# source_eagle.net
KiCad netlist of a schematic drawn in EAGLE
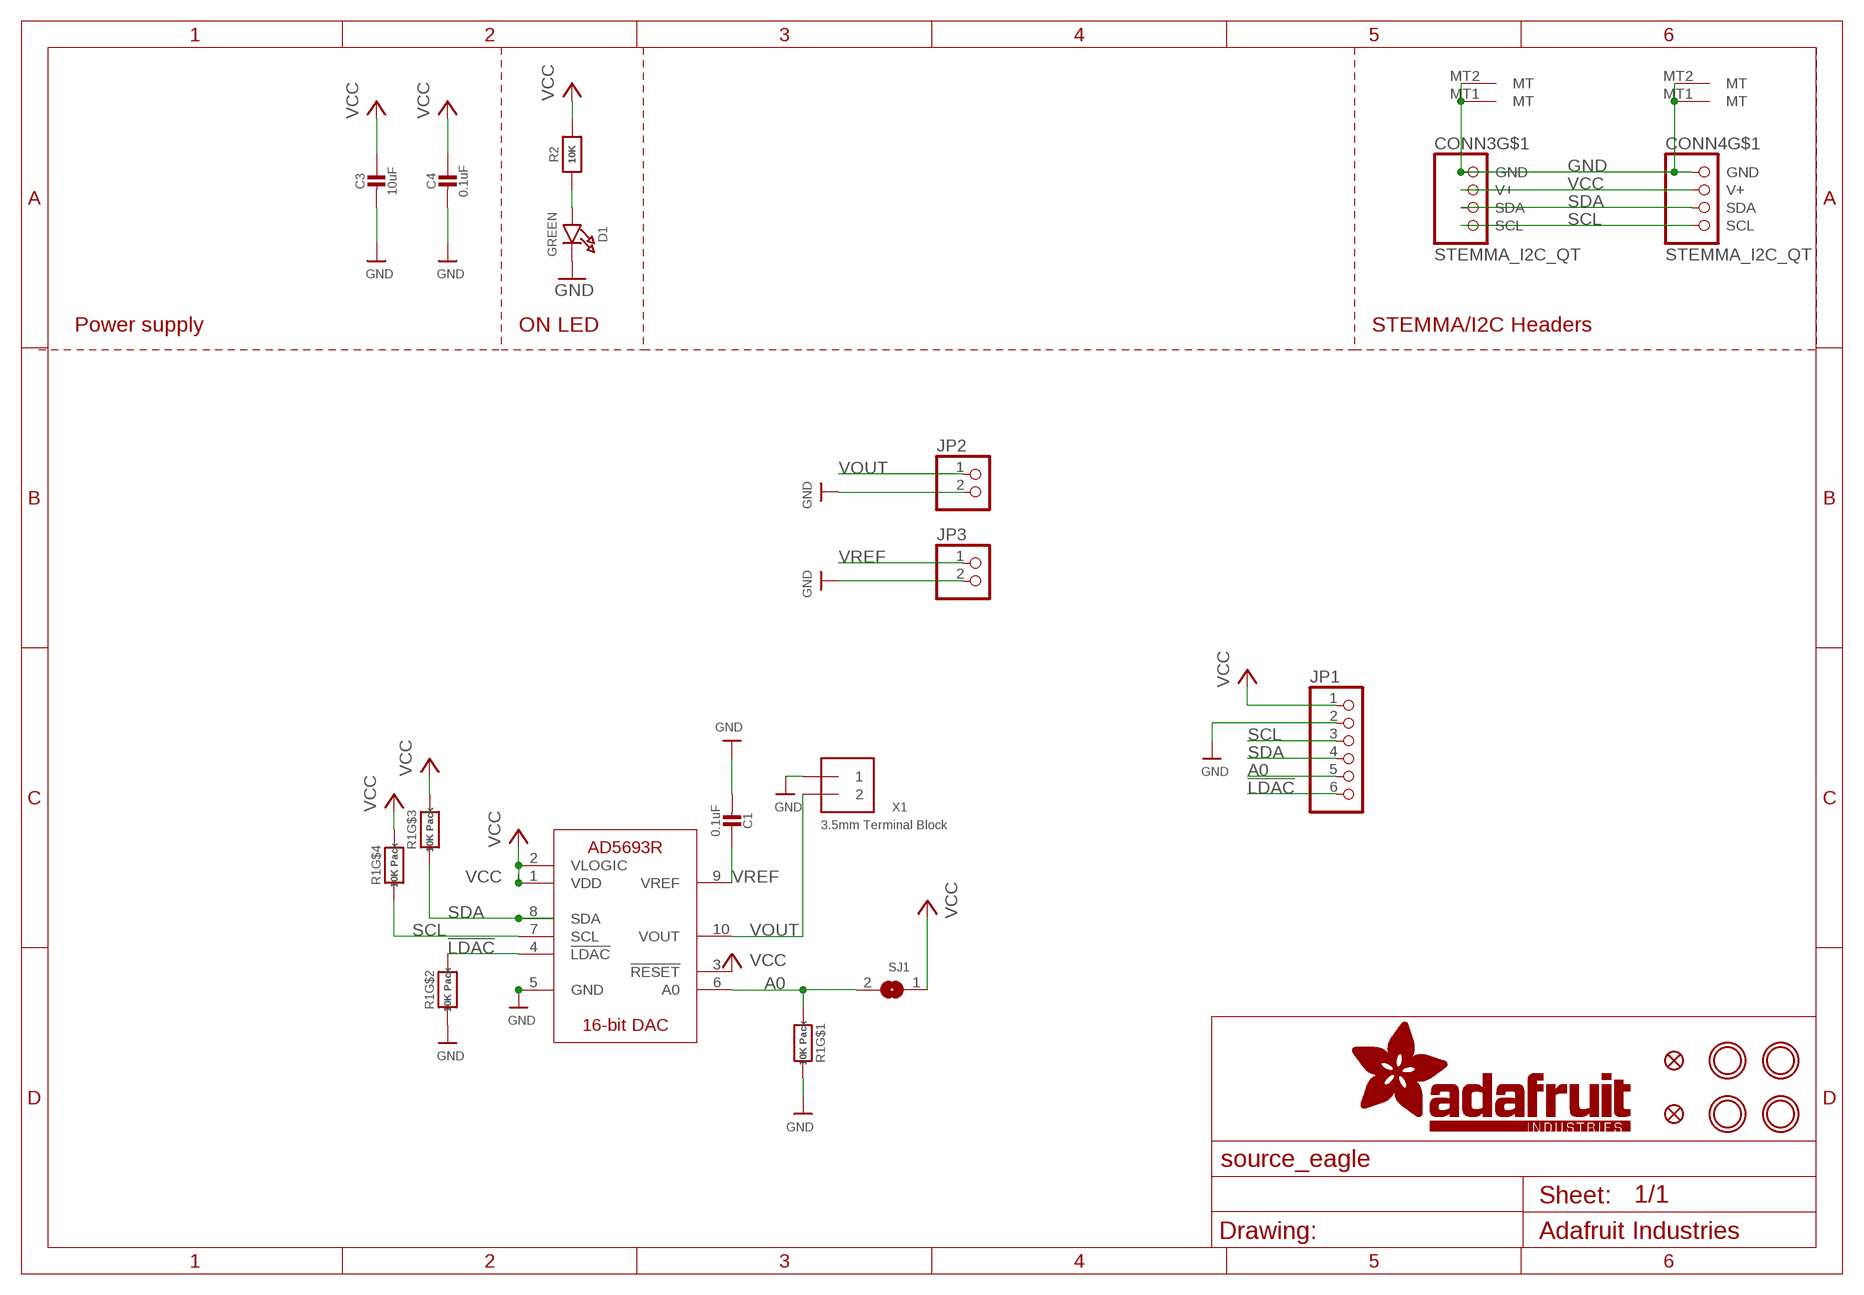
[diagram p0: schematic, sheet 1]

(export (version "E")
  (design (tool "Eeschema 10.0.6"))
  (components
    (comp (ref "C1")
      (value "0.1uF")
      (footprint "eagle-import:0603-NO")
      (libsource (lib "eagle-import") (part "CAP_CERAMIC0603_NO"))
    )
    (comp (ref "C3")
      (value "10uF")
      (footprint "eagle-import:0805-NO")
      (libsource (lib "eagle-import") (part "CAP_CERAMIC0805-NOOUTLINE"))
    )
    (comp (ref "C4")
      (value "0.1uF")
      (footprint "eagle-import:0603-NO")
      (libsource (lib "eagle-import") (part "CAP_CERAMIC0603_NO"))
    )
    (comp (ref "CONN3")
      (value "STEMMA_I2C_QT")
      (footprint "eagle-import:JST_SH4")
      (libsource (lib "eagle-import") (part "STEMMA_I2C_QT"))
    )
    (comp (ref "CONN4")
      (value "STEMMA_I2C_QT")
      (footprint "eagle-import:JST_SH4")
      (libsource (lib "eagle-import") (part "STEMMA_I2C_QT"))
    )
    (comp (ref "D1")
      (value "GREEN")
      (footprint "eagle-import:CHIPLED_0603_NOOUTLINE")
      (libsource (lib "eagle-import") (part "LED0603_NOOUTLINE"))
    )
    (comp (ref "FID3")
      (value "FIDUCIAL_1MM")
      (footprint "eagle-import:FIDUCIAL_1MM")
      (libsource (lib "eagle-import") (part "FIDUCIAL_1MM"))
    )
    (comp (ref "FID4")
      (value "FIDUCIAL_1MM")
      (footprint "eagle-import:FIDUCIAL_1MM")
      (libsource (lib "eagle-import") (part "FIDUCIAL_1MM"))
    )
    (comp (ref "IC2")
      (value "AD5693R_10PIN_RMZ")
      (footprint "eagle-import:MSOP10")
      (libsource (lib "eagle-import") (part "AD5693R_10PIN_RMZ"))
    )
    (comp (ref "JP1")
      (value "HEADER-1X670MIL")
      (footprint "eagle-import:1X06_ROUND_70")
      (libsource (lib "eagle-import") (part "HEADER-1X670MIL"))
    )
    (comp (ref "JP2")
      (value "HEADER-1X2ROUND")
      (footprint "eagle-import:1X02_ROUND")
      (libsource (lib "eagle-import") (part "HEADER-1X2ROUND"))
    )
    (comp (ref "JP3")
      (value "HEADER-1X2ROUND")
      (footprint "eagle-import:1X02_ROUND")
      (libsource (lib "eagle-import") (part "HEADER-1X2ROUND"))
    )
    (comp (ref "R1")
      (value "10K Pack")
      (footprint "eagle-import:RESPACK_4X0603")
      (libsource (lib "eagle-import") (part "RESISTOR_4PACK"))
    )
    (comp (ref "R2")
      (value "10K")
      (footprint "eagle-import:0603-NO")
      (libsource (lib "eagle-import") (part "RESISTOR_0603_NOOUT"))
    )
    (comp (ref "SJ1")
      (value "SOLDERJUMPER")
      (footprint "eagle-import:SOLDERJUMPER_ARROW_NOPASTE")
      (libsource (lib "eagle-import") (part "SOLDERJUMPER"))
    )
    (comp (ref "U$20")
      (value "MOUNTINGHOLE2.5")
      (footprint "eagle-import:MOUNTINGHOLE_2.5_PLATED")
      (libsource (lib "eagle-import") (part "MOUNTINGHOLE2.5"))
    )
    (comp (ref "U$21")
      (value "MOUNTINGHOLE2.5")
      (footprint "eagle-import:MOUNTINGHOLE_2.5_PLATED")
      (libsource (lib "eagle-import") (part "MOUNTINGHOLE2.5"))
    )
    (comp (ref "U$25")
      (value "MOUNTINGHOLE2.5")
      (footprint "eagle-import:MOUNTINGHOLE_2.5_PLATED")
      (libsource (lib "eagle-import") (part "MOUNTINGHOLE2.5"))
    )
    (comp (ref "U$27")
      (value "MOUNTINGHOLE2.5")
      (footprint "eagle-import:MOUNTINGHOLE_2.5_PLATED")
      (libsource (lib "eagle-import") (part "MOUNTINGHOLE2.5"))
    )
    (comp (ref "X1")
      (value "3.5mm Terminal Block")
      (footprint "eagle-import:TERMBLOCK_1X2-3.5MM")
      (libsource (lib "eagle-import") (part "TERMBLOCK_1X2_3.5MM"))
    )
  )
  (nets
    (net (code "1") (name "/A0") (class "Default")
      (node (ref "IC2") (pin "6") (pinfunction "A0_6") (pintype "input"))
      (node (ref "JP1") (pin "5") (pinfunction "5_5") (pintype "passive"))
      (node (ref "R1") (pin "8") (pinfunction "2_8") (pintype "passive"))
      (node (ref "SJ1") (pin "2") (pinfunction "2_2") (pintype "passive"))
    )
    (net (code "2") (name "/SCL") (class "Default")
      (node (ref "CONN3") (pin "4") (pinfunction "SCL_4") (pintype "passive"))
      (node (ref "CONN4") (pin "4") (pinfunction "SCL_4") (pintype "passive"))
      (node (ref "IC2") (pin "7") (pinfunction "SCL_7") (pintype "bidirectional"))
      (node (ref "JP1") (pin "3") (pinfunction "3_3") (pintype "passive"))
      (node (ref "R1") (pin "4") (pinfunction "1_4") (pintype "passive"))
    )
    (net (code "3") (name "/SDA") (class "Default")
      (node (ref "CONN3") (pin "3") (pinfunction "SDA_3") (pintype "passive"))
      (node (ref "CONN4") (pin "3") (pinfunction "SDA_3") (pintype "passive"))
      (node (ref "IC2") (pin "8") (pinfunction "SDA_8") (pintype "bidirectional"))
      (node (ref "JP1") (pin "4") (pinfunction "4_4") (pintype "passive"))
      (node (ref "R1") (pin "3") (pinfunction "1_3") (pintype "passive"))
    )
    (net (code "4") (name "/VOUT") (class "Default")
      (node (ref "IC2") (pin "10") (pinfunction "VOUT_10") (pintype "output"))
      (node (ref "JP2") (pin "1") (pinfunction "1_1") (pintype "passive"))
      (node (ref "X1") (pin "2") (pinfunction "2_2") (pintype "passive"))
    )
    (net (code "5") (name "/VREF") (class "Default")
      (node (ref "C1") (pin "1") (pinfunction "1_1") (pintype "passive"))
      (node (ref "IC2") (pin "9") (pinfunction "VREF_9") (pintype "power_in"))
      (node (ref "JP3") (pin "1") (pinfunction "1_1") (pintype "passive"))
    )
    (net (code "6") (name "/~{LDAC}") (class "Default")
      (node (ref "IC2") (pin "4") (pinfunction "~{LDAC}_4") (pintype "input"))
      (node (ref "JP1") (pin "6") (pinfunction "6_6") (pintype "passive"))
      (node (ref "R1") (pin "7") (pinfunction "2_7") (pintype "passive"))
    )
    (net (code "7") (name "GND") (class "Default")
      (node (ref "C1") (pin "2") (pinfunction "2_2") (pintype "passive"))
      (node (ref "C3") (pin "2") (pinfunction "2_2") (pintype "passive"))
      (node (ref "C4") (pin "2") (pinfunction "2_2") (pintype "passive"))
      (node (ref "CONN3") (pin "1") (pinfunction "GND_1") (pintype "passive"))
      (node (ref "CONN3") (pin "MT1") (pinfunction "MT_MT1") (pintype "bidirectional"))
      (node (ref "CONN3") (pin "MT2") (pinfunction "MT_MT2") (pintype "bidirectional"))
      (node (ref "CONN4") (pin "1") (pinfunction "GND_1") (pintype "passive"))
      (node (ref "CONN4") (pin "MT1") (pinfunction "MT_MT1") (pintype "bidirectional"))
      (node (ref "CONN4") (pin "MT2") (pinfunction "MT_MT2") (pintype "bidirectional"))
      (node (ref "D1") (pin "C") (pinfunction "C_C") (pintype "passive"))
      (node (ref "IC2") (pin "5") (pinfunction "GND_5") (pintype "power_in"))
      (node (ref "JP1") (pin "2") (pinfunction "2_2") (pintype "passive"))
      (node (ref "JP2") (pin "2") (pinfunction "2_2") (pintype "passive"))
      (node (ref "JP3") (pin "2") (pinfunction "2_2") (pintype "passive"))
      (node (ref "R1") (pin "1") (pinfunction "1_1") (pintype "passive"))
      (node (ref "R1") (pin "2") (pinfunction "1_2") (pintype "passive"))
      (node (ref "X1") (pin "1") (pinfunction "1_1") (pintype "passive"))
    )
    (net (code "8") (name "Net-(D1-PadA)") (class "Default")
      (node (ref "D1") (pin "A") (pinfunction "A_A") (pintype "passive"))
      (node (ref "R2") (pin "1") (pinfunction "1_1") (pintype "passive"))
    )
    (net (code "9") (name "VCC") (class "Default")
      (node (ref "C3") (pin "1") (pinfunction "1_1") (pintype "passive"))
      (node (ref "C4") (pin "1") (pinfunction "1_1") (pintype "passive"))
      (node (ref "CONN3") (pin "2") (pinfunction "V+_2") (pintype "passive"))
      (node (ref "CONN4") (pin "2") (pinfunction "V+_2") (pintype "passive"))
      (node (ref "IC2") (pin "1") (pinfunction "VDD_1") (pintype "power_in"))
      (node (ref "IC2") (pin "2") (pinfunction "VLOGIC_2") (pintype "power_in"))
      (node (ref "IC2") (pin "3") (pinfunction "~{RESET}_3") (pintype "input"))
      (node (ref "JP1") (pin "1") (pinfunction "1_1") (pintype "passive"))
      (node (ref "R1") (pin "5") (pinfunction "2_5") (pintype "passive"))
      (node (ref "R1") (pin "6") (pinfunction "2_6") (pintype "passive"))
      (node (ref "R2") (pin "2") (pinfunction "2_2") (pintype "passive"))
      (node (ref "SJ1") (pin "1") (pinfunction "1_1") (pintype "passive"))
    )
  )
)
